# Sedra.net
KiCad netlist of a schematic drawn in Altium Designer
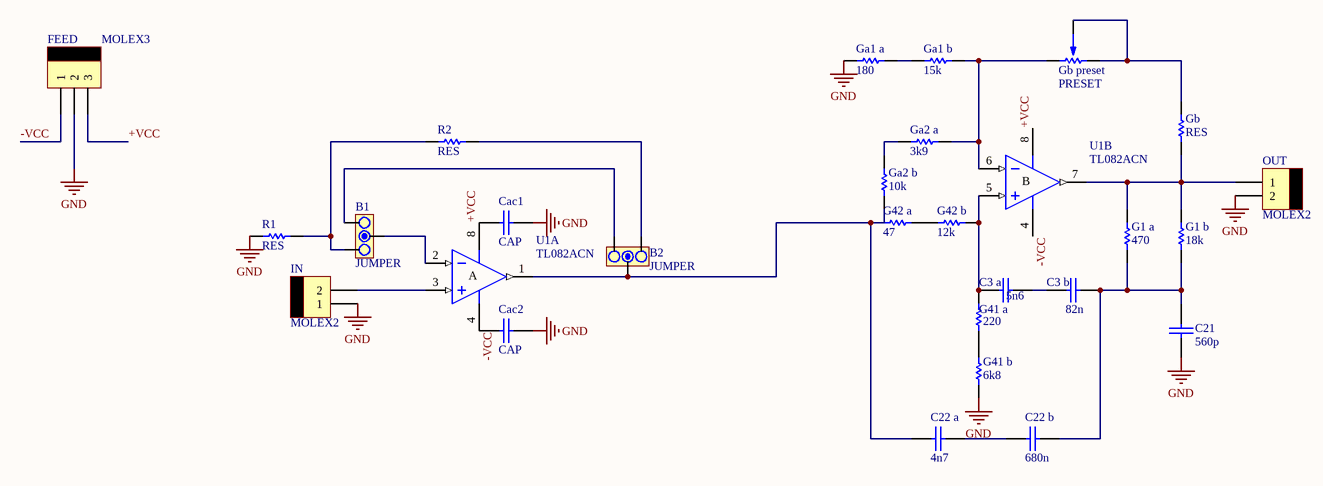
[diagram p0: Sedra.SchDoc]

(export (version "E")
  (design (tool "Eeschema 10.0.6"))
  (components
    (comp (ref "B1") (value "JUMPER") (footprint "JUMPER3") (libsource (lib "LIBEBAL") (part "JUMPER3")))
    (comp (ref "B2") (value "JUMPER") (footprint "JUMPER3") (libsource (lib "") (part "JUMPER3_1")))
    (comp (ref "C3 a") (value "5n6") (footprint "CAP200") (libsource (lib "LIBEBAL") (part "CAP")))
    (comp (ref "C3 b") (value "82n") (footprint "CAP200") (libsource (lib "LIBEBAL") (part "CAP")))
    (comp (ref "C21") (value "560p") (footprint "CAP200") (libsource (lib "LIBEBAL") (part "CAP")))
    (comp (ref "C22 a") (value "4n7") (footprint "CAP200") (libsource (lib "LIBEBAL") (part "CAP")))
    (comp (ref "C22 b") (value "680n") (footprint "CAP200") (libsource (lib "LIBEBAL") (part "CAP")))
    (comp (ref "Cac1") (value "CAP") (footprint "CAP200") (libsource (lib "LIBEBAL") (part "CAP")))
    (comp (ref "Cac2") (value "CAP") (footprint "CAP200") (libsource (lib "LIBEBAL") (part "CAP")))
    (comp (ref "FEED") (value "MOLEX3") (footprint "MOLEX3") (libsource (lib "LIBEBAL") (part "MOLEX3")))
    (comp (ref "G1 a") (value "470") (footprint "0805") (libsource (lib "LIBEBAL") (part "RES")))
    (comp (ref "G1 b") (value "18k") (footprint "0805") (libsource (lib "LIBEBAL") (part "RES")))
    (comp (ref "G41 a") (value "220") (footprint "0805") (libsource (lib "LIBEBAL") (part "RES")))
    (comp (ref "G41 b") (value "6k8") (footprint "0805") (libsource (lib "LIBEBAL") (part "RES")))
    (comp (ref "G42 a") (value "47") (footprint "0805") (libsource (lib "LIBEBAL") (part "RES")))
    (comp (ref "G42 b") (value "12k") (footprint "0805") (libsource (lib "LIBEBAL") (part "RES")))
    (comp (ref "Ga1 a") (value "180") (footprint "0805") (libsource (lib "LIBEBAL") (part "RES")))
    (comp (ref "Ga1 b") (value "15k") (footprint "0805") (libsource (lib "LIBEBAL") (part "RES")))
    (comp (ref "Ga2 a") (value "3k9") (footprint "0805") (libsource (lib "LIBEBAL") (part "RES")))
    (comp (ref "Ga2 b") (value "10k") (footprint "0805") (libsource (lib "LIBEBAL") (part "RES")))
    (comp (ref "Gb") (value "RES") (footprint "0805") (libsource (lib "LIBEBAL") (part "RES")))
    (comp (ref "Gb preset")
      (value "PRESET")
      (footprint "PRESET V")
      (libsource (lib "LIBEBAL") (part "PRESET"))
    )
    (comp (ref "IN") (value "MOLEX2") (footprint "MOLEX2") (libsource (lib "") (part "MOLEX2_1")))
    (comp (ref "OUT") (value "MOLEX2") (footprint "MOLEX2") (libsource (lib "LIBEBAL") (part "MOLEX2")))
    (comp (ref "R1") (value "RES") (footprint "0805") (libsource (lib "LIBEBAL") (part "RES")))
    (comp (ref "R2") (value "RES") (footprint "0805") (libsource (lib "LIBEBAL") (part "RES")))
    (comp (ref "U1")
      (value "TL082ACN")
      (footprint "DIP8")
      (description "General-Purpose J-FET Dual Operational Amplifier")
      (fields (field (name "PUBLISHER") "Altium Limited"))
      (libsource (lib "ST Operational Amplifier") (part "TL082ACN"))
    )
  )
  (nets
    (net (code "1") (name "/+VCC") (class "Default")
      (node (ref "Cac1") (pin "1") (pinfunction "1_1") (pintype "passive"))
      (node (ref "FEED") (pin "3") (pinfunction "3_3") (pintype "passive"))
      (node (ref "U1") (pin "8") (pinfunction "V+_8") (pintype "power_in"))
    )
    (net (code "2") (name "/-VCC") (class "Default")
      (node (ref "Cac2") (pin "1") (pinfunction "1_1") (pintype "passive"))
      (node (ref "FEED") (pin "1") (pinfunction "1_1") (pintype "passive"))
      (node (ref "U1") (pin "4") (pinfunction "V-_4") (pintype "power_in"))
    )
    (net (code "3") (name "GND") (class "Default")
      (node (ref "C21") (pin "2") (pinfunction "2_2") (pintype "passive"))
      (node (ref "Cac1") (pin "2") (pinfunction "2_2") (pintype "passive"))
      (node (ref "Cac2") (pin "2") (pinfunction "2_2") (pintype "passive"))
      (node (ref "FEED") (pin "2") (pinfunction "2_2") (pintype "passive"))
      (node (ref "G41 b") (pin "1") (pinfunction "1_1") (pintype "passive"))
      (node (ref "Ga1 a") (pin "1") (pinfunction "1_1") (pintype "passive"))
      (node (ref "IN") (pin "1") (pinfunction "1_1") (pintype "passive"))
      (node (ref "OUT") (pin "2") (pinfunction "2_2") (pintype "passive"))
      (node (ref "R1") (pin "1") (pinfunction "1_1") (pintype "passive"))
    )
    (net (code "4") (name "Net-(B1-Pad1)") (class "Default")
      (node (ref "B1") (pin "1") (pinfunction "1_1") (pintype "passive"))
      (node (ref "R1") (pin "2") (pinfunction "2_2") (pintype "passive"))
      (node (ref "R2") (pin "1") (pinfunction "1_1") (pintype "passive"))
    )
    (net (code "5") (name "Net-(B1-Pad3)") (class "Default")
      (node (ref "B1") (pin "3") (pinfunction "3_3") (pintype "passive"))
      (node (ref "B2") (pin "1") (pinfunction "1_1") (pintype "passive"))
    )
    (net (code "6") (name "Net-(B2-Pad3)") (class "Default")
      (node (ref "B2") (pin "3") (pinfunction "3_3") (pintype "passive"))
      (node (ref "R2") (pin "2") (pinfunction "2_2") (pintype "passive"))
    )
    (net (code "7") (name "Net-(C3 a-Pad2)") (class "Default")
      (node (ref "C3 a") (pin "2") (pinfunction "2_2") (pintype "passive"))
      (node (ref "C3 b") (pin "1") (pinfunction "1_1") (pintype "passive"))
    )
    (net (code "8") (name "Net-(C21-Pad1)") (class "Default")
      (node (ref "C21") (pin "1") (pinfunction "1_1") (pintype "passive"))
      (node (ref "C22 b") (pin "2") (pinfunction "2_2") (pintype "passive"))
      (node (ref "C3 b") (pin "2") (pinfunction "2_2") (pintype "passive"))
      (node (ref "G1 a") (pin "1") (pinfunction "1_1") (pintype "passive"))
      (node (ref "G1 b") (pin "1") (pinfunction "1_1") (pintype "passive"))
    )
    (net (code "9") (name "Net-(C22 a-Pad2)") (class "Default")
      (node (ref "C22 a") (pin "2") (pinfunction "2_2") (pintype "passive"))
      (node (ref "C22 b") (pin "1") (pinfunction "1_1") (pintype "passive"))
    )
    (net (code "10") (name "Net-(G41 a-Pad1)") (class "Default")
      (node (ref "G41 a") (pin "1") (pinfunction "1_1") (pintype "passive"))
      (node (ref "G41 b") (pin "2") (pinfunction "2_2") (pintype "passive"))
    )
    (net (code "11") (name "Net-(G42 a-Pad2)") (class "Default")
      (node (ref "G42 a") (pin "2") (pinfunction "2_2") (pintype "passive"))
      (node (ref "G42 b") (pin "1") (pinfunction "1_1") (pintype "passive"))
    )
    (net (code "12") (name "Net-(Ga1 a-Pad2)") (class "Default")
      (node (ref "Ga1 a") (pin "2") (pinfunction "2_2") (pintype "passive"))
      (node (ref "Ga1 b") (pin "1") (pinfunction "1_1") (pintype "passive"))
    )
    (net (code "13") (name "Net-(Ga2 a-Pad1)") (class "Default")
      (node (ref "Ga2 a") (pin "1") (pinfunction "1_1") (pintype "passive"))
      (node (ref "Ga2 b") (pin "2") (pinfunction "2_2") (pintype "passive"))
    )
    (net (code "14") (name "Net-(Gb preset-Pad2)") (class "Default")
      (node (ref "Gb") (pin "2") (pinfunction "2_2") (pintype "passive"))
      (node (ref "Gb preset") (pin "2") (pinfunction "2_2") (pintype "passive"))
      (node (ref "Gb preset") (pin "3") (pinfunction "3_3") (pintype "passive"))
    )
    (net (code "15") (name "Net-(U1A-IN+)") (class "Default")
      (node (ref "IN") (pin "2") (pinfunction "2_2") (pintype "passive"))
      (node (ref "U1") (pin "3") (pinfunction "IN+_3") (pintype "input"))
    )
    (net (code "16") (name "Net-(U1A-IN-)") (class "Default")
      (node (ref "B1") (pin "2") (pinfunction "2_2") (pintype "passive"))
      (node (ref "U1") (pin "2") (pinfunction "IN-_2") (pintype "input"))
    )
    (net (code "17") (name "Net-(U1A-OUT)") (class "Default")
      (node (ref "B2") (pin "2") (pinfunction "2_2") (pintype "passive"))
      (node (ref "C22 a") (pin "1") (pinfunction "1_1") (pintype "passive"))
      (node (ref "G42 a") (pin "1") (pinfunction "1_1") (pintype "passive"))
      (node (ref "Ga2 b") (pin "1") (pinfunction "1_1") (pintype "passive"))
      (node (ref "U1") (pin "1") (pinfunction "OUT_1") (pintype "output"))
    )
    (net (code "18") (name "Net-(U1B-IN+)") (class "Default")
      (node (ref "C3 a") (pin "1") (pinfunction "1_1") (pintype "passive"))
      (node (ref "G41 a") (pin "2") (pinfunction "2_2") (pintype "passive"))
      (node (ref "G42 b") (pin "2") (pinfunction "2_2") (pintype "passive"))
      (node (ref "U1") (pin "5") (pinfunction "IN+_5") (pintype "input"))
    )
    (net (code "19") (name "Net-(U1B-IN-)") (class "Default")
      (node (ref "Ga1 b") (pin "2") (pinfunction "2_2") (pintype "passive"))
      (node (ref "Ga2 a") (pin "2") (pinfunction "2_2") (pintype "passive"))
      (node (ref "Gb preset") (pin "1") (pinfunction "1_1") (pintype "passive"))
      (node (ref "U1") (pin "6") (pinfunction "IN-_6") (pintype "input"))
    )
    (net (code "20") (name "Net-(U1B-OUT)") (class "Default")
      (node (ref "G1 a") (pin "2") (pinfunction "2_2") (pintype "passive"))
      (node (ref "G1 b") (pin "2") (pinfunction "2_2") (pintype "passive"))
      (node (ref "Gb") (pin "1") (pinfunction "1_1") (pintype "passive"))
      (node (ref "OUT") (pin "1") (pinfunction "1_1") (pintype "passive"))
      (node (ref "U1") (pin "7") (pinfunction "OUT_7") (pintype "output"))
    )
  )
)
